# EN_Boot_Buttons.net
KiCad netlist of a schematic drawn in Altium Designer
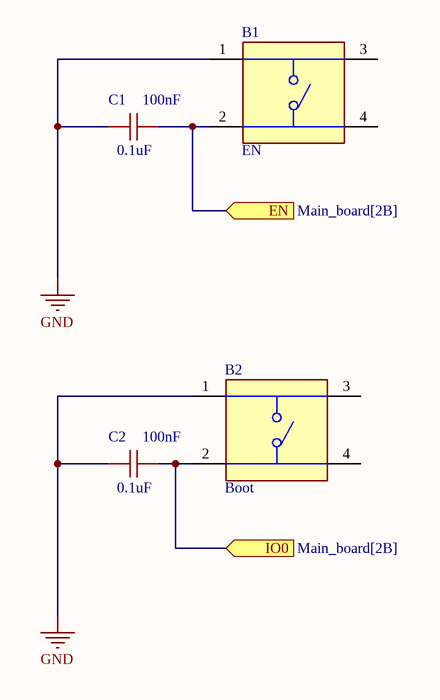
[diagram p0: EN_Boot_Buttons.SchDoc]

(export (version "E")
  (design (tool "Eeschema 10.0.6"))
  (components
    (comp (ref "B1")
      (value "EN")
      (footprint "SW_TS04-66-43-BK-100-SMT")
      (description "6 x 6 mm, 5 mm Actuator Height, 160 gf, Black, Surface Mount, SPST, Tactile Switch")
      (fields
        (field (name "MANUFACTURER") "Same Sky")
        (field (name "MANUFACTURER PART NUMBER") "TS04-66-50-BK-160-SMT-TR")
      )
      (libsource (lib "ESP32") (part "TS04-66-50-BK-160-SMT-TR_1"))
    )
    (comp (ref "B2")
      (value "Boot")
      (footprint "SW_TS04-66-43-BK-100-SMT")
      (description "6 x 6 mm, 5 mm Actuator Height, 160 gf, Black, Surface Mount, SPST, Tactile Switch")
      (fields
        (field (name "MANUFACTURER") "Same Sky")
        (field (name "MANUFACTURER PART NUMBER") "TS04-66-50-BK-160-SMT-TR")
      )
      (libsource (lib "ESP32") (part "TS04-66-50-BK-160-SMT-TR_1"))
    )
    (comp (ref "C1")
      (value "100nF")
      (footprint "CAPC2013X140X45ML15T25")
      (description "Ceramic Capacitor, Ceramic, 25V, 10% +Tol, 10% -Tol, X7R, 15% TC, 0.1uF, Surface Mount, 0805")
      (fields
        (field (name "MANUFACTURER") "Murata")
        (field (name "MANUFACTURER PART NUMBER") "GCM21BR71E104KA37L")
      )
      (libsource (lib "ESP32") (part "GCM21BR71E104KA37L"))
    )
    (comp (ref "C2")
      (value "100nF")
      (footprint "CAPC2013X140X45ML15T25")
      (description "Ceramic Capacitor, Ceramic, 25V, 10% +Tol, 10% -Tol, X7R, 15% TC, 0.1uF, Surface Mount, 0805")
      (fields
        (field (name "MANUFACTURER") "Murata")
        (field (name "MANUFACTURER PART NUMBER") "GCM21BR71E104KA37L")
      )
      (libsource (lib "ESP32") (part "GCM21BR71E104KA37L"))
    )
  )
  (nets
    (net (code "1") (name "/EN") (class "Default")
      (node (ref "B1") (pin "2") (pinfunction "2_2") (pintype "passive"))
      (node (ref "C1") (pin "2") (pinfunction "2_2") (pintype "passive"))
    )
    (net (code "2") (name "/IO0") (class "Default")
      (node (ref "B2") (pin "2") (pinfunction "2_2") (pintype "passive"))
      (node (ref "C2") (pin "2") (pinfunction "2_2") (pintype "passive"))
    )
    (net (code "3") (name "GND") (class "Default")
      (node (ref "B1") (pin "1") (pinfunction "1_1") (pintype "passive"))
      (node (ref "B2") (pin "1") (pinfunction "1_1") (pintype "passive"))
      (node (ref "C1") (pin "1") (pinfunction "1_1") (pintype "passive"))
      (node (ref "C2") (pin "1") (pinfunction "1_1") (pintype "passive"))
    )
    (net (code "4") (name "unconnected-(B1-Pad3)") (class "Default")
      (node (ref "B1") (pin "3") (pinfunction "3_3") (pintype "passive"))
    )
    (net (code "5") (name "unconnected-(B1-Pad4)") (class "Default")
      (node (ref "B1") (pin "4") (pinfunction "4_4") (pintype "passive"))
    )
    (net (code "6") (name "unconnected-(B2-Pad3)") (class "Default")
      (node (ref "B2") (pin "3") (pinfunction "3_3") (pintype "passive"))
    )
    (net (code "7") (name "unconnected-(B2-Pad4)") (class "Default")
      (node (ref "B2") (pin "4") (pinfunction "4_4") (pintype "passive"))
    )
  )
)
